# Mainsnode_v2_wifi_rev_a.net
KiCad netlist of a schematic drawn in EAGLE
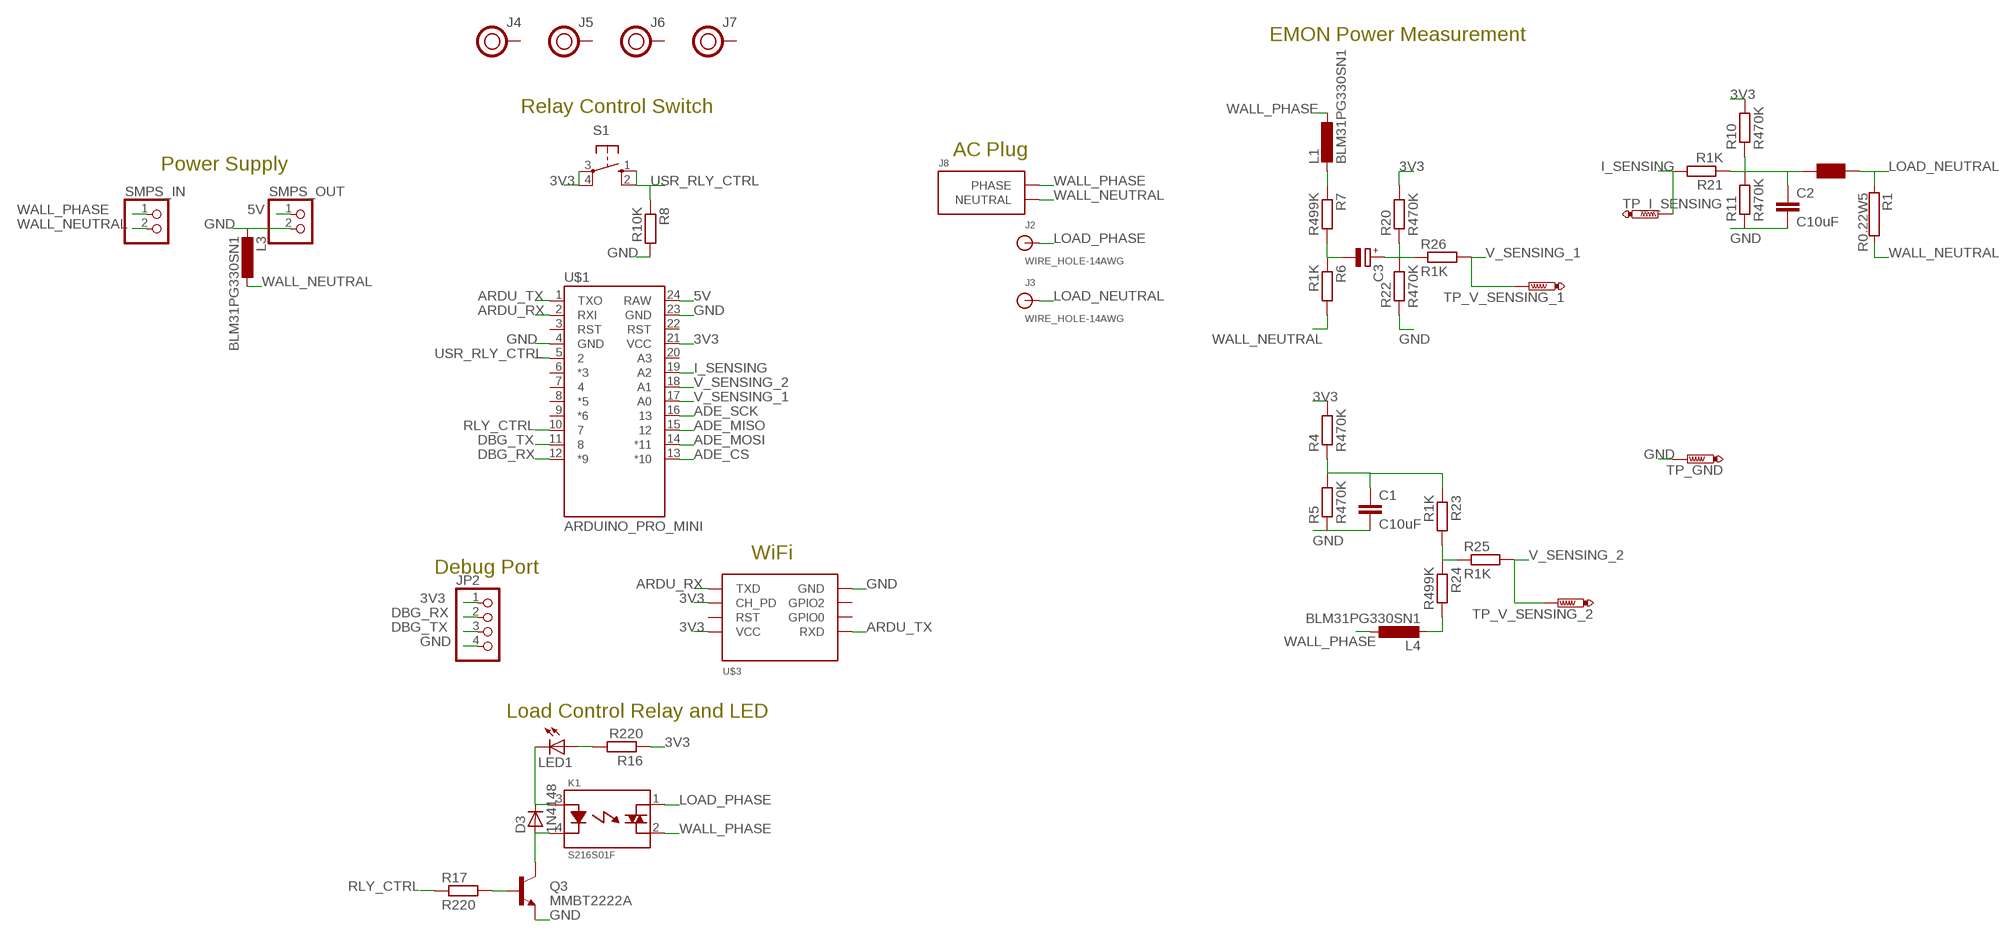
[diagram p0: schematic, sheet 1]

(export (version "E")
  (design (tool "Eeschema 10.0.6"))
  (components
    (comp (ref "C1")
      (value "C10uF")
      (footprint "eagle-import:C0805")
      (libsource (lib "eagle-import") (part "C-EUC0805"))
    )
    (comp (ref "C2")
      (value "C10uF")
      (footprint "eagle-import:C0805")
      (libsource (lib "eagle-import") (part "C-EUC0805"))
    )
    (comp (ref "C3")
      (value "CPOL-EU140CLH-0810")
      (footprint "eagle-import:140CLH-0810")
      (libsource (lib "eagle-import") (part "CPOL-EU140CLH-0810"))
    )
    (comp (ref "D3")
      (value "1N4148")
      (footprint "eagle-import:SOD80")
      (libsource (lib "eagle-import") (part "D-SOD-80"))
    )
    (comp (ref "J2")
      (value "WIRE_HOLE-14AWG")
      (footprint "eagle-import:WIRE_HOLE-14AWG")
      (libsource (lib "eagle-import") (part "WIRE_HOLE-14AWG"))
    )
    (comp (ref "J3")
      (value "WIRE_HOLE-14AWG")
      (footprint "eagle-import:WIRE_HOLE-14AWG")
      (libsource (lib "eagle-import") (part "WIRE_HOLE-14AWG"))
    )
    (comp (ref "J4")
      (value "HOLE")
      (footprint "eagle-import:HOLE-0.125")
      (libsource (lib "eagle-import") (part "HOLE"))
    )
    (comp (ref "J5")
      (value "HOLE")
      (footprint "eagle-import:HOLE-0.125")
      (libsource (lib "eagle-import") (part "HOLE"))
    )
    (comp (ref "J6")
      (value "HOLE")
      (footprint "eagle-import:HOLE-0.125")
      (libsource (lib "eagle-import") (part "HOLE"))
    )
    (comp (ref "J7")
      (value "HOLE")
      (footprint "eagle-import:HOLE-0.125")
      (libsource (lib "eagle-import") (part "HOLE"))
    )
    (comp (ref "J8")
      (value "AC-PLUG-2")
      (footprint "eagle-import:AC_MALE_PINS_2")
      (libsource (lib "eagle-import") (part "AC-PLUG-2"))
    )
    (comp (ref "JP2")
      (value "PINHD-1X4")
      (footprint "eagle-import:1X04")
      (libsource (lib "eagle-import") (part "PINHD-1X4"))
    )
    (comp (ref "K1")
      (value "S216S01F")
      (footprint "eagle-import:RELAY_SX16S0X")
      (libsource (lib "eagle-import") (part "S216S01F"))
    )
    (comp (ref "L1")
      (value "BLM31PG330SN1")
      (footprint "eagle-import:L3216C")
      (libsource (lib "eagle-import") (part "L-EUL3216C"))
    )
    (comp (ref "L3")
      (value "BLM31PG330SN1")
      (footprint "eagle-import:L3216C")
      (libsource (lib "eagle-import") (part "L-EUL3216C"))
    )
    (comp (ref "L4")
      (value "BLM31PG330SN1")
      (footprint "eagle-import:L3216C")
      (libsource (lib "eagle-import") (part "L-EUL3216C"))
    )
    (comp (ref "LED1")
      (value "LED3MM")
      (footprint "eagle-import:LED3MM")
      (libsource (lib "eagle-import") (part "LED3MM"))
    )
    (comp (ref "Q3")
      (value "MMBT2222A")
      (footprint "eagle-import:SOT23-3")
      (libsource (lib "eagle-import") (part "TRANSISTOR_NPNMMBT2222A"))
    )
    (comp (ref "R1")
      (value "R0.22W5")
      (footprint "eagle-import:KH206-8")
      (libsource (lib "eagle-import") (part "RKH206-8"))
    )
    (comp (ref "R4")
      (value "R470K")
      (footprint "eagle-import:R0805")
      (libsource (lib "eagle-import") (part "R-EU_R0805"))
    )
    (comp (ref "R5")
      (value "R470K")
      (footprint "eagle-import:R0805")
      (libsource (lib "eagle-import") (part "R-EU_R0805"))
    )
    (comp (ref "R6")
      (value "R1K")
      (footprint "eagle-import:R0805")
      (libsource (lib "eagle-import") (part "R-EU_R0805"))
    )
    (comp (ref "R7")
      (value "R499K")
      (footprint "eagle-import:R0805")
      (libsource (lib "eagle-import") (part "R-EU_R0805"))
    )
    (comp (ref "R8")
      (value "R10K")
      (footprint "eagle-import:R0805")
      (libsource (lib "eagle-import") (part "R-EU_R0805"))
    )
    (comp (ref "R10")
      (value "R470K")
      (footprint "eagle-import:R0805")
      (libsource (lib "eagle-import") (part "R-EU_R0805"))
    )
    (comp (ref "R11")
      (value "R470K")
      (footprint "eagle-import:R0805")
      (libsource (lib "eagle-import") (part "R-EU_R0805"))
    )
    (comp (ref "R16")
      (value "R220")
      (footprint "eagle-import:R0805")
      (libsource (lib "eagle-import") (part "R-EU_R0805"))
    )
    (comp (ref "R17")
      (value "R220")
      (footprint "eagle-import:R0805")
      (libsource (lib "eagle-import") (part "R-EU_R0805"))
    )
    (comp (ref "R20")
      (value "R470K")
      (footprint "eagle-import:R0805")
      (libsource (lib "eagle-import") (part "R-EU_R0805"))
    )
    (comp (ref "R21")
      (value "R1K")
      (footprint "eagle-import:R0805")
      (libsource (lib "eagle-import") (part "R-EU_R0805"))
    )
    (comp (ref "R22")
      (value "R470K")
      (footprint "eagle-import:R0805")
      (libsource (lib "eagle-import") (part "R-EU_R0805"))
    )
    (comp (ref "R23")
      (value "R1K")
      (footprint "eagle-import:R0805")
      (libsource (lib "eagle-import") (part "R-EU_R0805"))
    )
    (comp (ref "R24")
      (value "R499K")
      (footprint "eagle-import:R0805")
      (libsource (lib "eagle-import") (part "R-EU_R0805"))
    )
    (comp (ref "R25")
      (value "R1K")
      (footprint "eagle-import:R0805")
      (libsource (lib "eagle-import") (part "R-EU_R0805"))
    )
    (comp (ref "R26")
      (value "R1K")
      (footprint "eagle-import:R0805")
      (libsource (lib "eagle-import") (part "R-EU_R0805"))
    )
    (comp (ref "S1")
      (value "10-XX")
      (footprint "eagle-import:B3F-10XX")
      (fields (field (name "MPN") "B3F-1000"))
      (libsource (lib "eagle-import") (part "10-XX"))
    )
    (comp (ref "SMPS_IN")
      (value "PINHD-1X2")
      (footprint "eagle-import:1X02")
      (libsource (lib "eagle-import") (part "PINHD-1X2"))
    )
    (comp (ref "SMPS_OUT")
      (value "PINHD-1X2")
      (footprint "eagle-import:1X02")
      (libsource (lib "eagle-import") (part "PINHD-1X2"))
    )
    (comp (ref "TP_GND")
      (value "PTR1PAD1-13")
      (footprint "eagle-import:P1-13")
      (libsource (lib "eagle-import") (part "PTR1PAD1-13"))
    )
    (comp (ref "TP_I_SENSING")
      (value "PTR1PAD1-13")
      (footprint "eagle-import:P1-13")
      (libsource (lib "eagle-import") (part "PTR1PAD1-13"))
    )
    (comp (ref "TP_V_SENSING_1")
      (value "PTR1PAD1-13")
      (footprint "eagle-import:P1-13")
      (libsource (lib "eagle-import") (part "PTR1PAD1-13"))
    )
    (comp (ref "TP_V_SENSING_2")
      (value "PTR1PAD1-13")
      (footprint "eagle-import:P1-13")
      (libsource (lib "eagle-import") (part "PTR1PAD1-13"))
    )
    (comp (ref "U$1")
      (value "ARDUINO_PRO_MINI")
      (footprint "eagle-import:ARDUINO_PRO_MINI")
      (libsource (lib "eagle-import") (part "ARDUINO_PRO_MINI"))
    )
    (comp (ref "U$2")
      (value "BLM18BB151SN1")
      (footprint "eagle-import:L0603")
      (libsource (lib "eagle-import") (part "L0603"))
    )
    (comp (ref "U$3")
      (value "ESP8266")
      (footprint "eagle-import:ESP8266")
      (libsource (lib "eagle-import") (part "ESP8266"))
    )
  )
  (nets
    (net (code "1") (name "/3V3") (class "Default")
      (node (ref "JP2") (pin "1") (pinfunction "1_1") (pintype "passive"))
      (node (ref "R10") (pin "2") (pinfunction "2_2") (pintype "passive"))
      (node (ref "R16") (pin "1") (pinfunction "1_1") (pintype "passive"))
      (node (ref "R20") (pin "2") (pinfunction "2_2") (pintype "passive"))
      (node (ref "R4") (pin "2") (pinfunction "2_2") (pintype "passive"))
      (node (ref "S1") (pin "3") (pinfunction "P_3") (pintype "passive"))
      (node (ref "S1") (pin "4") (pinfunction "P1_4") (pintype "passive"))
      (node (ref "U$1") (pin "21") (pinfunction "VCC_21") (pintype "bidirectional"))
      (node (ref "U$3") (pin "CH_PD") (pinfunction "CH_PD_CH_PD") (pintype "bidirectional"))
      (node (ref "U$3") (pin "VCC") (pinfunction "VCC_VCC") (pintype "bidirectional"))
    )
    (net (code "2") (name "/5V") (class "Default")
      (node (ref "SMPS_OUT") (pin "1") (pinfunction "1_1") (pintype "passive"))
      (node (ref "U$1") (pin "24") (pinfunction "RAW_24") (pintype "bidirectional"))
    )
    (net (code "3") (name "/ADE_CS") (class "Default")
      (node (ref "U$1") (pin "13") (pinfunction "*10_13") (pintype "bidirectional"))
    )
    (net (code "4") (name "/ADE_MISO") (class "Default")
      (node (ref "U$1") (pin "15") (pinfunction "12_15") (pintype "bidirectional"))
    )
    (net (code "5") (name "/ADE_MOSI") (class "Default")
      (node (ref "U$1") (pin "14") (pinfunction "*11_14") (pintype "bidirectional"))
    )
    (net (code "6") (name "/ADE_SCK") (class "Default")
      (node (ref "U$1") (pin "16") (pinfunction "13_16") (pintype "bidirectional"))
    )
    (net (code "7") (name "/ARDU_RX") (class "Default")
      (node (ref "U$1") (pin "2") (pinfunction "RXI_2") (pintype "bidirectional"))
      (node (ref "U$3") (pin "TXD") (pinfunction "TXD_TXD") (pintype "bidirectional"))
    )
    (net (code "8") (name "/ARDU_TX") (class "Default")
      (node (ref "U$1") (pin "1") (pinfunction "TXO_1") (pintype "bidirectional"))
      (node (ref "U$3") (pin "RXD") (pinfunction "RXD_RXD") (pintype "bidirectional"))
    )
    (net (code "9") (name "/DBG_RX") (class "Default")
      (node (ref "JP2") (pin "2") (pinfunction "2_2") (pintype "passive"))
      (node (ref "U$1") (pin "12") (pinfunction "*9_12") (pintype "bidirectional"))
    )
    (net (code "10") (name "/DBG_TX") (class "Default")
      (node (ref "JP2") (pin "3") (pinfunction "3_3") (pintype "passive"))
      (node (ref "U$1") (pin "11") (pinfunction "8_11") (pintype "bidirectional"))
    )
    (net (code "11") (name "/GND") (class "Default")
      (node (ref "C1") (pin "2") (pinfunction "2_2") (pintype "passive"))
      (node (ref "C2") (pin "2") (pinfunction "2_2") (pintype "passive"))
      (node (ref "JP2") (pin "4") (pinfunction "4_4") (pintype "passive"))
      (node (ref "L3") (pin "2") (pinfunction "2_2") (pintype "passive"))
      (node (ref "Q3") (pin "2") (pinfunction "E_2") (pintype "passive"))
      (node (ref "R11") (pin "1") (pinfunction "1_1") (pintype "passive"))
      (node (ref "R22") (pin "1") (pinfunction "1_1") (pintype "passive"))
      (node (ref "R5") (pin "1") (pinfunction "1_1") (pintype "passive"))
      (node (ref "R8") (pin "2") (pinfunction "2_2") (pintype "passive"))
      (node (ref "SMPS_OUT") (pin "2") (pinfunction "2_2") (pintype "passive"))
      (node (ref "TP_GND") (pin "TP") (pinfunction "TP_TP") (pintype "input"))
      (node (ref "U$1") (pin "23") (pinfunction "GND_23") (pintype "bidirectional"))
      (node (ref "U$1") (pin "4") (pinfunction "GND_4") (pintype "bidirectional"))
      (node (ref "U$3") (pin "GND") (pinfunction "GND_GND") (pintype "bidirectional"))
    )
    (net (code "12") (name "/I_SENSING") (class "Default")
      (node (ref "R21") (pin "2") (pinfunction "2_2") (pintype "passive"))
      (node (ref "TP_I_SENSING") (pin "TP") (pinfunction "TP_TP") (pintype "input"))
      (node (ref "U$1") (pin "19") (pinfunction "A2_19") (pintype "bidirectional"))
    )
    (net (code "13") (name "/LOAD_NEUTRAL") (class "Default")
      (node (ref "J3") (pin "P$1") (pinfunction "P$1_P$1") (pintype "bidirectional"))
      (node (ref "R1") (pin "1") (pinfunction "1_1") (pintype "passive"))
      (node (ref "U$2") (pin "2") (pinfunction "P$2_2") (pintype "bidirectional"))
    )
    (net (code "14") (name "/LOAD_PHASE") (class "Default")
      (node (ref "J2") (pin "P$1") (pinfunction "P$1_P$1") (pintype "bidirectional"))
      (node (ref "K1") (pin "1") (pinfunction "1_1") (pintype "bidirectional"))
    )
    (net (code "15") (name "/RLY_CTRL") (class "Default")
      (node (ref "R17") (pin "1") (pinfunction "1_1") (pintype "passive"))
      (node (ref "U$1") (pin "10") (pinfunction "7_10") (pintype "bidirectional"))
    )
    (net (code "16") (name "/USR_RLY_CTRL") (class "Default")
      (node (ref "R8") (pin "1") (pinfunction "1_1") (pintype "passive"))
      (node (ref "S1") (pin "1") (pinfunction "S_1") (pintype "passive"))
      (node (ref "S1") (pin "2") (pinfunction "S1_2") (pintype "passive"))
      (node (ref "U$1") (pin "5") (pinfunction "2_5") (pintype "bidirectional"))
    )
    (net (code "17") (name "/V_SENSING_1") (class "Default")
      (node (ref "R26") (pin "2") (pinfunction "2_2") (pintype "passive"))
      (node (ref "TP_V_SENSING_1") (pin "TP") (pinfunction "TP_TP") (pintype "input"))
      (node (ref "U$1") (pin "17") (pinfunction "A0_17") (pintype "bidirectional"))
    )
    (net (code "18") (name "/V_SENSING_2") (class "Default")
      (node (ref "R25") (pin "2") (pinfunction "2_2") (pintype "passive"))
      (node (ref "TP_V_SENSING_2") (pin "TP") (pinfunction "TP_TP") (pintype "input"))
      (node (ref "U$1") (pin "18") (pinfunction "A1_18") (pintype "bidirectional"))
    )
    (net (code "19") (name "/WALL_NEUTRAL") (class "Default")
      (node (ref "J8") (pin "WALL_NEUTRAL") (pinfunction "NEUTRAL_WALL_NEUTRAL") (pintype "bidirectional"))
      (node (ref "L3") (pin "1") (pinfunction "1_1") (pintype "passive"))
      (node (ref "R1") (pin "2") (pinfunction "2_2") (pintype "passive"))
      (node (ref "R6") (pin "2") (pinfunction "2_2") (pintype "passive"))
      (node (ref "SMPS_IN") (pin "2") (pinfunction "2_2") (pintype "passive"))
    )
    (net (code "20") (name "/WALL_PHASE") (class "Default")
      (node (ref "J8") (pin "WALL_PHASE") (pinfunction "PHASE_WALL_PHASE") (pintype "bidirectional"))
      (node (ref "K1") (pin "2") (pinfunction "2_2") (pintype "bidirectional"))
      (node (ref "L1") (pin "1") (pinfunction "1_1") (pintype "passive"))
      (node (ref "L4") (pin "1") (pinfunction "1_1") (pintype "passive"))
      (node (ref "SMPS_IN") (pin "1") (pinfunction "1_1") (pintype "passive"))
    )
    (net (code "21") (name "Net-(C1-Pad1)") (class "Default")
      (node (ref "C1") (pin "1") (pinfunction "1_1") (pintype "passive"))
      (node (ref "R23") (pin "1") (pinfunction "1_1") (pintype "passive"))
      (node (ref "R4") (pin "1") (pinfunction "1_1") (pintype "passive"))
      (node (ref "R5") (pin "2") (pinfunction "2_2") (pintype "passive"))
    )
    (net (code "22") (name "Net-(C3-Pad+)") (class "Default")
      (node (ref "C3") (pin "+") (pinfunction "+_+") (pintype "passive"))
      (node (ref "R20") (pin "1") (pinfunction "1_1") (pintype "passive"))
      (node (ref "R22") (pin "2") (pinfunction "2_2") (pintype "passive"))
      (node (ref "R26") (pin "1") (pinfunction "1_1") (pintype "passive"))
    )
    (net (code "23") (name "Net-(C3-Pad-)") (class "Default")
      (node (ref "C3") (pin "-") (pinfunction "-_-") (pintype "passive"))
      (node (ref "R6") (pin "1") (pinfunction "1_1") (pintype "passive"))
      (node (ref "R7") (pin "2") (pinfunction "2_2") (pintype "passive"))
    )
    (net (code "24") (name "Net-(D3-A)") (class "Default")
      (node (ref "D3") (pin "2") (pinfunction "A_2") (pintype "passive"))
      (node (ref "K1") (pin "4") (pinfunction "4_4") (pintype "bidirectional"))
      (node (ref "Q3") (pin "3") (pinfunction "C_3") (pintype "passive"))
    )
    (net (code "25") (name "Net-(D3-C)") (class "Default")
      (node (ref "D3") (pin "1") (pinfunction "C_1") (pintype "passive"))
      (node (ref "K1") (pin "3") (pinfunction "3_3") (pintype "bidirectional"))
      (node (ref "LED1") (pin "K") (pinfunction "C_K") (pintype "passive"))
    )
    (net (code "26") (name "Net-(L1-Pad2)") (class "Default")
      (node (ref "L1") (pin "2") (pinfunction "2_2") (pintype "passive"))
      (node (ref "R7") (pin "1") (pinfunction "1_1") (pintype "passive"))
    )
    (net (code "27") (name "Net-(L4-Pad2)") (class "Default")
      (node (ref "L4") (pin "2") (pinfunction "2_2") (pintype "passive"))
      (node (ref "R24") (pin "2") (pinfunction "2_2") (pintype "passive"))
    )
    (net (code "28") (name "Net-(LED1-PadA)") (class "Default")
      (node (ref "LED1") (pin "A") (pinfunction "A_A") (pintype "passive"))
      (node (ref "R16") (pin "2") (pinfunction "2_2") (pintype "passive"))
    )
    (net (code "29") (name "Net-(Q3-B)") (class "Default")
      (node (ref "Q3") (pin "1") (pinfunction "B_1") (pintype "passive"))
      (node (ref "R17") (pin "2") (pinfunction "2_2") (pintype "passive"))
    )
    (net (code "30") (name "Net-(R23-Pad2)") (class "Default")
      (node (ref "R23") (pin "2") (pinfunction "2_2") (pintype "passive"))
      (node (ref "R24") (pin "1") (pinfunction "1_1") (pintype "passive"))
      (node (ref "R25") (pin "1") (pinfunction "1_1") (pintype "passive"))
    )
    (net (code "31") (name "Net-(U$2-P$1)") (class "Default")
      (node (ref "C2") (pin "1") (pinfunction "1_1") (pintype "passive"))
      (node (ref "R10") (pin "1") (pinfunction "1_1") (pintype "passive"))
      (node (ref "R11") (pin "2") (pinfunction "2_2") (pintype "passive"))
      (node (ref "R21") (pin "1") (pinfunction "1_1") (pintype "passive"))
      (node (ref "U$2") (pin "1") (pinfunction "P$1_1") (pintype "bidirectional"))
    )
    (net (code "32") (name "unconnected-(J4-P$1-Pad1)") (class "Default")
      (node (ref "J4") (pin "1") (pinfunction "P$1_1") (pintype "bidirectional"))
    )
    (net (code "33") (name "unconnected-(J5-P$1-Pad1)") (class "Default")
      (node (ref "J5") (pin "1") (pinfunction "P$1_1") (pintype "bidirectional"))
    )
    (net (code "34") (name "unconnected-(J6-P$1-Pad1)") (class "Default")
      (node (ref "J6") (pin "1") (pinfunction "P$1_1") (pintype "bidirectional"))
    )
    (net (code "35") (name "unconnected-(J7-P$1-Pad1)") (class "Default")
      (node (ref "J7") (pin "1") (pinfunction "P$1_1") (pintype "bidirectional"))
    )
    (net (code "36") (name "unconnected-(U$1-*3-Pad6)") (class "Default")
      (node (ref "U$1") (pin "6") (pinfunction "*3_6") (pintype "bidirectional"))
    )
    (net (code "37") (name "unconnected-(U$1-*5-Pad8)") (class "Default")
      (node (ref "U$1") (pin "8") (pinfunction "*5_8") (pintype "bidirectional"))
    )
    (net (code "38") (name "unconnected-(U$1-*6-Pad9)") (class "Default")
      (node (ref "U$1") (pin "9") (pinfunction "*6_9") (pintype "bidirectional"))
    )
    (net (code "39") (name "unconnected-(U$1-4-Pad7)") (class "Default")
      (node (ref "U$1") (pin "7") (pinfunction "4_7") (pintype "bidirectional"))
    )
    (net (code "40") (name "unconnected-(U$1-A3-Pad20)") (class "Default")
      (node (ref "U$1") (pin "20") (pinfunction "A3_20") (pintype "bidirectional"))
    )
    (net (code "41") (name "unconnected-(U$1-RST-Pad3)") (class "Default")
      (node (ref "U$1") (pin "3") (pinfunction "RST_3") (pintype "bidirectional"))
    )
    (net (code "42") (name "unconnected-(U$1-RST-Pad22)") (class "Default")
      (node (ref "U$1") (pin "22") (pinfunction "RST_22") (pintype "bidirectional"))
    )
    (net (code "43") (name "unconnected-(U$3-PadGPIO0)") (class "Default")
      (node (ref "U$3") (pin "GPIO0") (pinfunction "GPIO0_GPIO0") (pintype "bidirectional"))
    )
    (net (code "44") (name "unconnected-(U$3-PadGPIO2)") (class "Default")
      (node (ref "U$3") (pin "GPIO2") (pinfunction "GPIO2_GPIO2") (pintype "bidirectional"))
    )
    (net (code "45") (name "unconnected-(U$3-PadRST)") (class "Default")
      (node (ref "U$3") (pin "RST") (pinfunction "RST_RST") (pintype "bidirectional"))
    )
  )
)
